# TopLevelProcessor400.net
KiCad netlist of a schematic drawn in Altium Designer
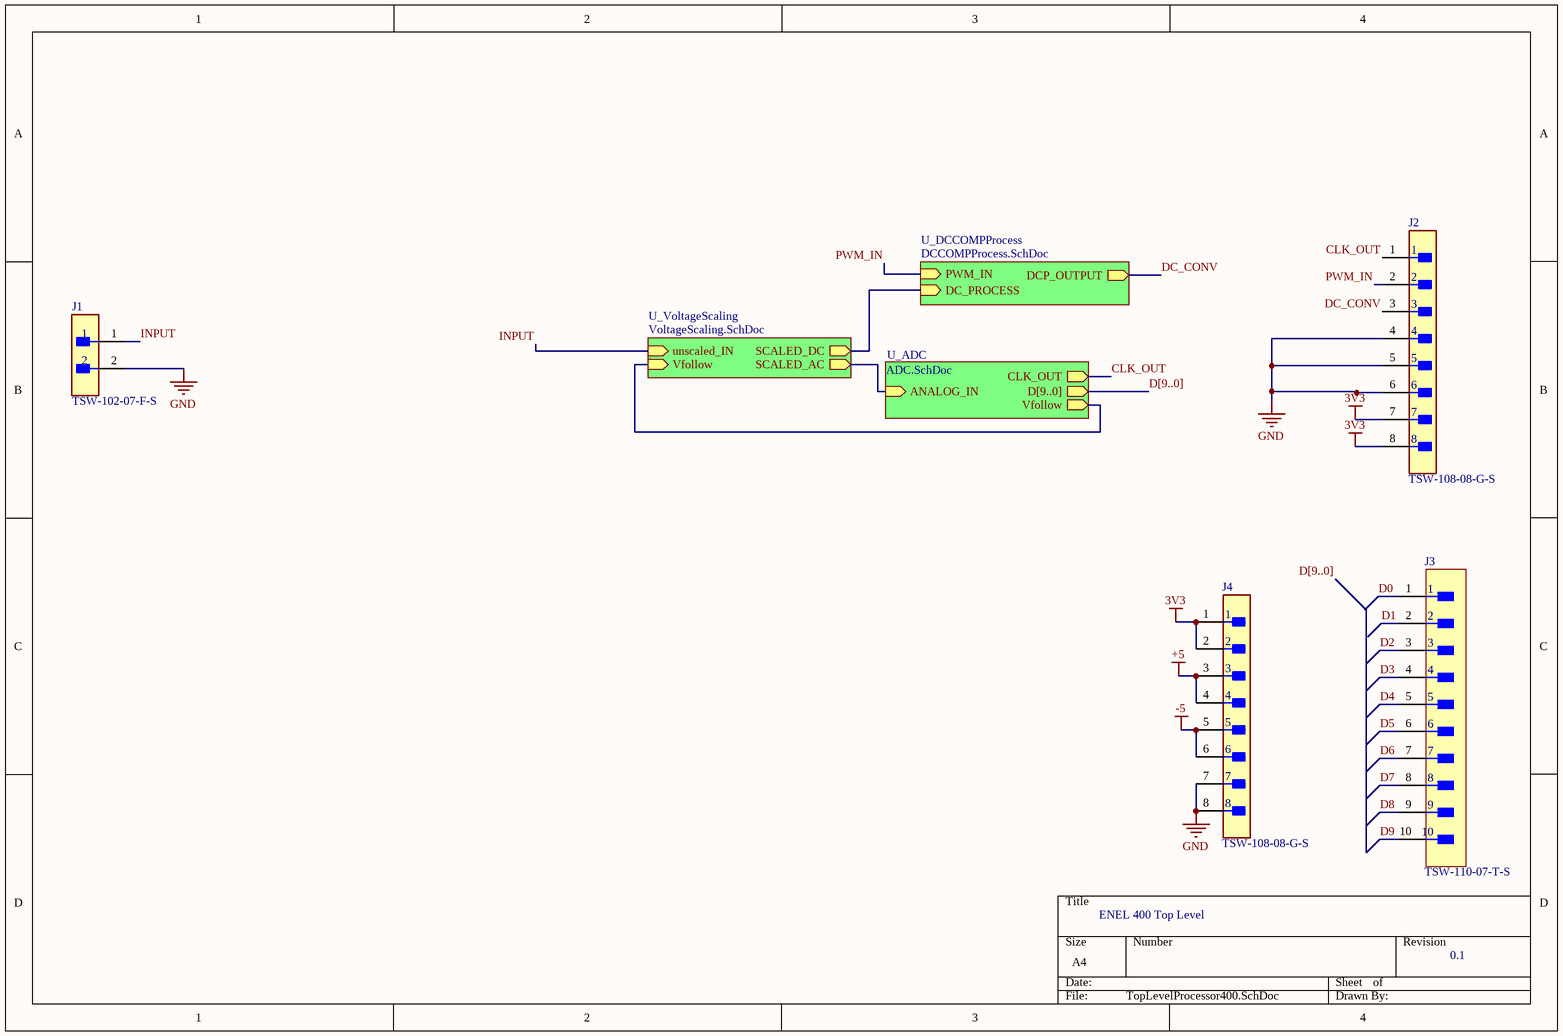
[diagram p0: TopLevelProcessor400.SchDoc]

(export (version "E")
  (design (tool "Eeschema 10.0.6"))
  (components
    (comp (ref "J1")
      (value "TSW-102-07-F-S")
      (footprint "FP-TSW-102-07-F-S-MFG")
      (description "CONN HEADER VERT 2POS 2.54MM")
      (libsource (lib "Altium Content Vault") (part "3bc925449376181038e59eaffc5286c"))
    )
    (comp (ref "J2")
      (value "TSW-108-08-G-S")
      (footprint "FP-TSW-108-08-G-S-MFG")
      (description "CONN HEADER VERT 8POS 2.54MM")
      (fields
        (field (name "MANUFACTURER") "Samtec")
        (field (name "OCTOPART") "https://octopart.com/tsw-108-08-g-s-samtec-272653")
      )
      (libsource (lib "Altium Content Vault") (part "99ec2b232beb5d2356d4d77f6a047f0"))
    )
    (comp (ref "J3")
      (value "TSW-110-07-T-S")
      (footprint "FP-TSW-110-07-T-S-MFG")
      (description "TSW-110-07-T-S TSW - Samtec 2.54mm Pin Header 10.92mm Overall Pin Length (07) (mcv)(TO22)")
      (libsource (lib "Altium Content Vault") (part "TSW-110-07-T-S"))
    )
    (comp (ref "J4")
      (value "TSW-108-08-G-S")
      (footprint "FP-TSW-108-08-G-S-MFG")
      (description "CONN HEADER VERT 8POS 2.54MM")
      (fields
        (field (name "MANUFACTURER") "Samtec")
        (field (name "OCTOPART") "https://octopart.com/tsw-108-08-g-s-samtec-272653")
      )
      (libsource (lib "Altium Content Vault") (part "99ec2b232beb5d2356d4d77f6a047f0"))
    )
  )
  (nets
    (net (code "1") (name "+5") (class "Default")
      (node (ref "J4") (pin "3") (pinfunction "3_3") (pintype "passive"))
      (node (ref "J4") (pin "4") (pinfunction "4_4") (pintype "passive"))
    )
    (net (code "2") (name "-5") (class "Default")
      (node (ref "J4") (pin "5") (pinfunction "5_5") (pintype "passive"))
      (node (ref "J4") (pin "6") (pinfunction "6_6") (pintype "passive"))
    )
    (net (code "3") (name "/CLK_OUT") (class "Default")
      (node (ref "J2") (pin "1") (pinfunction "1_1") (pintype "passive"))
    )
    (net (code "4") (name "/D0") (class "Default")
      (node (ref "J3") (pin "1") (pinfunction "1_1") (pintype "passive"))
    )
    (net (code "5") (name "/D1") (class "Default")
      (node (ref "J3") (pin "2") (pinfunction "2_2") (pintype "passive"))
    )
    (net (code "6") (name "/D2") (class "Default")
      (node (ref "J3") (pin "3") (pinfunction "3_3") (pintype "passive"))
    )
    (net (code "7") (name "/D3") (class "Default")
      (node (ref "J3") (pin "4") (pinfunction "4_4") (pintype "passive"))
    )
    (net (code "8") (name "/D4") (class "Default")
      (node (ref "J3") (pin "5") (pinfunction "5_5") (pintype "passive"))
    )
    (net (code "9") (name "/D5") (class "Default")
      (node (ref "J3") (pin "6") (pinfunction "6_6") (pintype "passive"))
    )
    (net (code "10") (name "/D6") (class "Default")
      (node (ref "J3") (pin "7") (pinfunction "7_7") (pintype "passive"))
    )
    (net (code "11") (name "/D7") (class "Default")
      (node (ref "J3") (pin "8") (pinfunction "8_8") (pintype "passive"))
    )
    (net (code "12") (name "/D8") (class "Default")
      (node (ref "J3") (pin "9") (pinfunction "9_9") (pintype "passive"))
    )
    (net (code "13") (name "/D9") (class "Default")
      (node (ref "J3") (pin "10") (pinfunction "10_10") (pintype "passive"))
    )
    (net (code "14") (name "/DC_CONV") (class "Default")
      (node (ref "J2") (pin "3") (pinfunction "3_3") (pintype "passive"))
    )
    (net (code "16") (name "/INPUT") (class "Default")
      (node (ref "J1") (pin "1") (pinfunction "1_1") (pintype "passive"))
    )
    (net (code "17") (name "/PWM_IN") (class "Default")
      (node (ref "J2") (pin "2") (pinfunction "2_2") (pintype "passive"))
    )
    (net (code "21") (name "3V3") (class "Default")
      (node (ref "J2") (pin "7") (pinfunction "7_7") (pintype "passive"))
      (node (ref "J2") (pin "8") (pinfunction "8_8") (pintype "passive"))
      (node (ref "J4") (pin "1") (pinfunction "1_1") (pintype "passive"))
      (node (ref "J4") (pin "2") (pinfunction "2_2") (pintype "passive"))
    )
    (net (code "22") (name "GND") (class "Default")
      (node (ref "J1") (pin "2") (pinfunction "2_2") (pintype "passive"))
      (node (ref "J2") (pin "4") (pinfunction "4_4") (pintype "passive"))
      (node (ref "J2") (pin "5") (pinfunction "5_5") (pintype "passive"))
      (node (ref "J2") (pin "6") (pinfunction "6_6") (pintype "passive"))
      (node (ref "J4") (pin "7") (pinfunction "7_7") (pintype "passive"))
      (node (ref "J4") (pin "8") (pinfunction "8_8") (pintype "passive"))
    )
  )
)
